# view-board.net
KiCad netlist of a schematic drawn in EAGLE
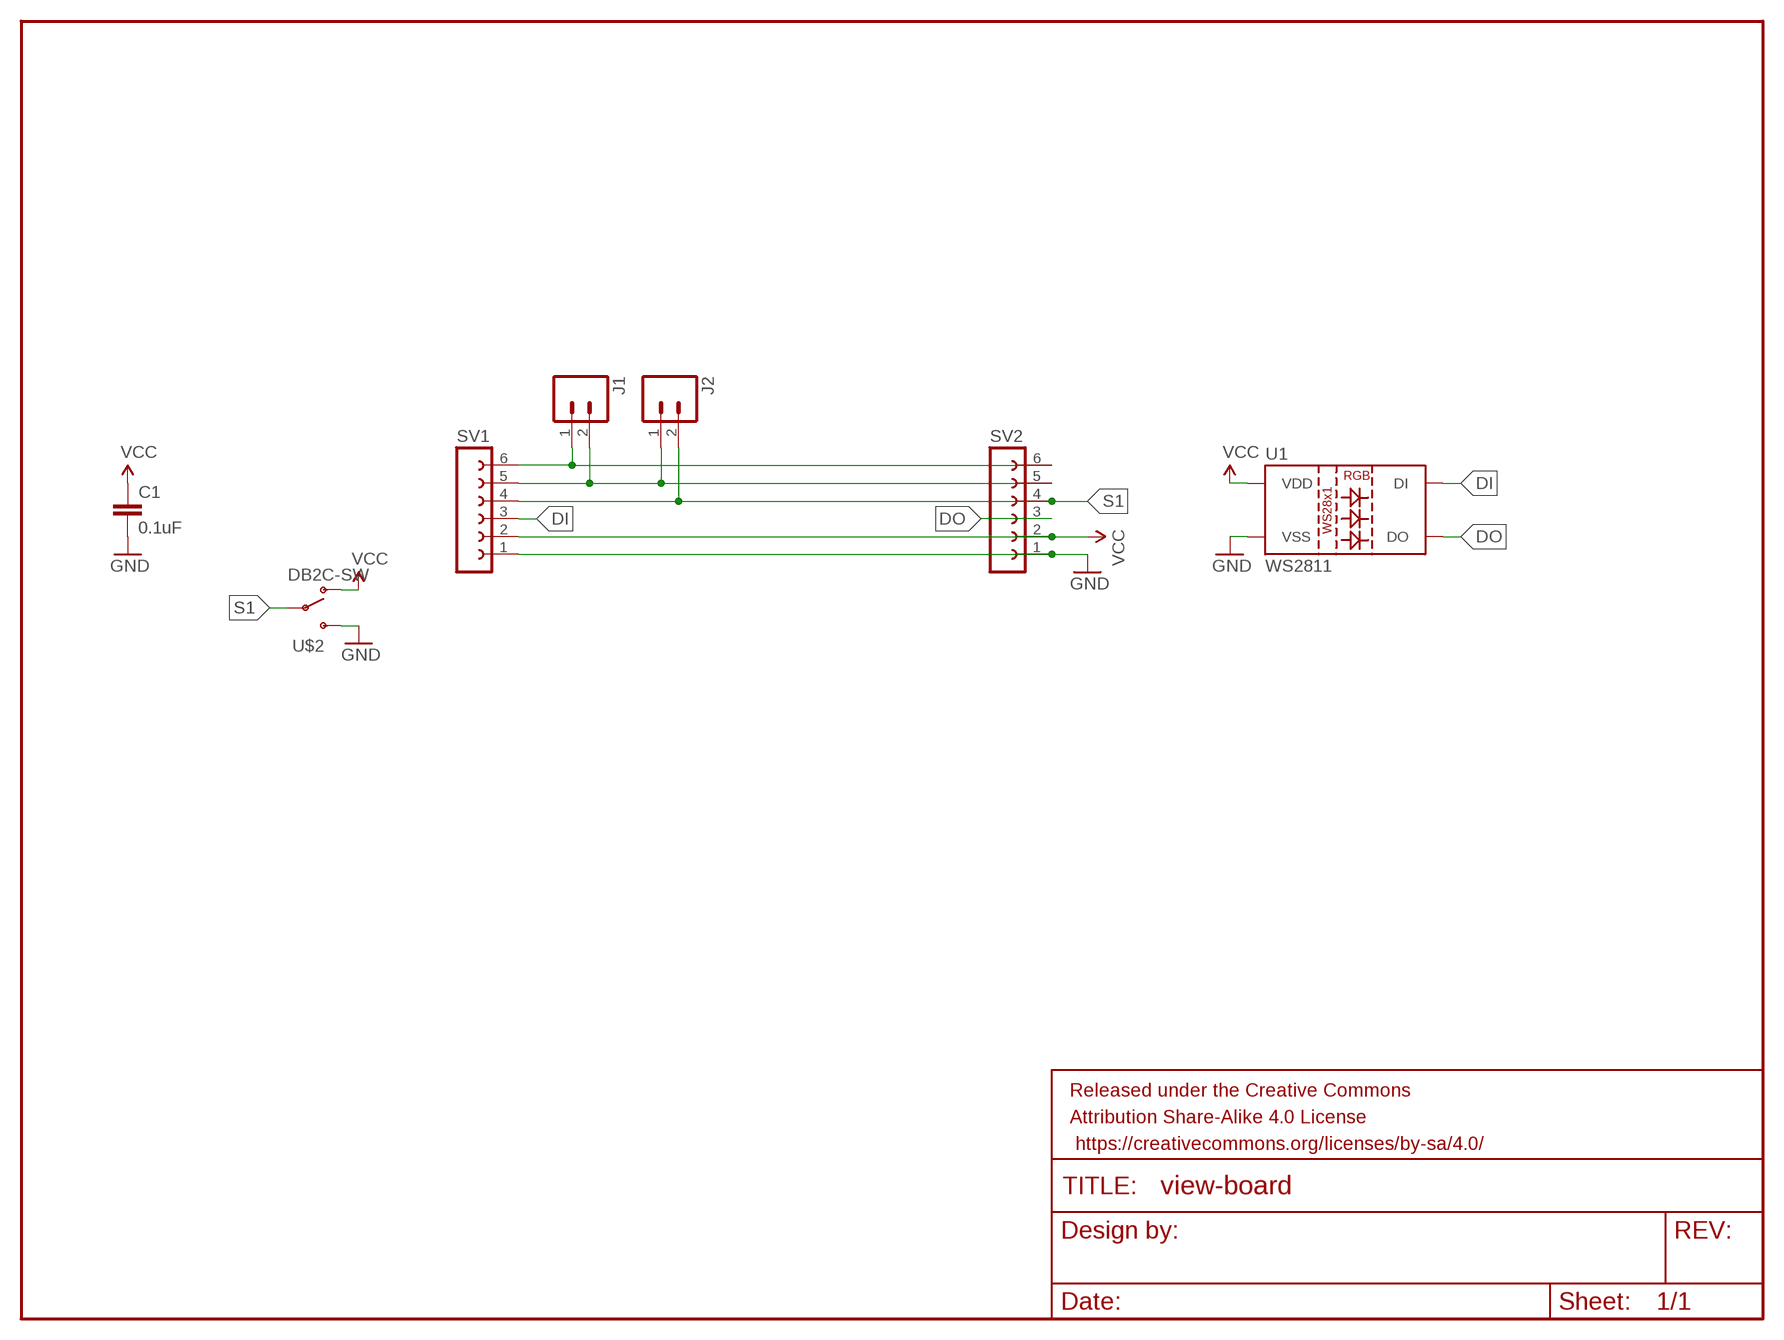
[diagram p0: schematic, sheet 1]

(export (version "E")
  (design (tool "Eeschema 10.0.6"))
  (components
    (comp (ref "C1")
      (value "0.1uF")
      (footprint "eagle-import:0805")
      (libsource (lib "eagle-import") (part "CAP0805"))
    )
    (comp (ref "FRAME1")
      (value "FRAME-LETTER")
      (footprint "eagle-import:CREATIVE_COMMONS")
      (libsource (lib "eagle-import") (part "FRAME-LETTER"))
    )
    (comp (ref "J1")
      (value "M02LOCK")
      (footprint "eagle-import:1X02_LOCK")
      (libsource (lib "eagle-import") (part "M02LOCK"))
    )
    (comp (ref "J2")
      (value "M02LOCK")
      (footprint "eagle-import:1X02_LOCK")
      (libsource (lib "eagle-import") (part "M02LOCK"))
    )
    (comp (ref "SV1")
      (value "FE06-1")
      (footprint "eagle-import:FE06")
      (libsource (lib "eagle-import") (part "FE06-1"))
    )
    (comp (ref "SV2")
      (value "FE06-1")
      (footprint "eagle-import:FE06")
      (libsource (lib "eagle-import") (part "FE06-1"))
    )
    (comp (ref "U$2")
      (value "DB2C-SW")
      (footprint "eagle-import:CHERRY-DB2C")
      (libsource (lib "eagle-import") (part "DB2C-SW"))
    )
    (comp (ref "U1")
      (value "WS2811")
      (footprint "eagle-import:LED-TRICOLOR-5050-IC")
      (libsource (lib "eagle-import") (part "LED-TRICOLOR-5050-ICWS2811"))
    )
  )
  (nets
    (net (code "1") (name "DI") (class "Default")
      (node (ref "SV1") (pin "3") (pinfunction "3_3") (pintype "passive"))
      (node (ref "U1") (pin "2") (pinfunction "DI_2") (pintype "bidirectional"))
    )
    (net (code "2") (name "DO") (class "Default")
      (node (ref "SV2") (pin "3") (pinfunction "3_3") (pintype "passive"))
      (node (ref "U1") (pin "1") (pinfunction "DO_1") (pintype "bidirectional"))
    )
    (net (code "3") (name "GND") (class "Default")
      (node (ref "C1") (pin "2") (pinfunction "2_2") (pintype "passive"))
      (node (ref "SV1") (pin "1") (pinfunction "1_1") (pintype "passive"))
      (node (ref "SV2") (pin "1") (pinfunction "1_1") (pintype "passive"))
      (node (ref "U$2") (pin "3") (pinfunction "S_3") (pintype "passive"))
      (node (ref "U1") (pin "6") (pinfunction "VSS_6") (pintype "bidirectional"))
    )
    (net (code "4") (name "Net-(J1-Pad1)") (class "Default")
      (node (ref "J1") (pin "1") (pinfunction "1_1") (pintype "passive"))
      (node (ref "SV1") (pin "6") (pinfunction "6_6") (pintype "passive"))
      (node (ref "SV2") (pin "6") (pinfunction "6_6") (pintype "passive"))
    )
    (net (code "5") (name "Net-(J1-Pad2)") (class "Default")
      (node (ref "J1") (pin "2") (pinfunction "2_2") (pintype "passive"))
      (node (ref "J2") (pin "1") (pinfunction "1_1") (pintype "passive"))
      (node (ref "SV1") (pin "5") (pinfunction "5_5") (pintype "passive"))
      (node (ref "SV2") (pin "5") (pinfunction "5_5") (pintype "passive"))
    )
    (net (code "6") (name "S1") (class "Default")
      (node (ref "J2") (pin "2") (pinfunction "2_2") (pintype "passive"))
      (node (ref "SV1") (pin "4") (pinfunction "4_4") (pintype "passive"))
      (node (ref "SV2") (pin "4") (pinfunction "4_4") (pintype "passive"))
      (node (ref "U$2") (pin "2") (pinfunction "P_2") (pintype "passive"))
    )
    (net (code "7") (name "VCC") (class "Default")
      (node (ref "C1") (pin "1") (pinfunction "1_1") (pintype "passive"))
      (node (ref "SV1") (pin "2") (pinfunction "2_2") (pintype "passive"))
      (node (ref "SV2") (pin "2") (pinfunction "2_2") (pintype "passive"))
      (node (ref "U$2") (pin "1") (pinfunction "O_1") (pintype "passive"))
      (node (ref "U1") (pin "3") (pinfunction "VDD_3") (pintype "bidirectional"))
      (node (ref "U1") (pin "5") (pinfunction "VDD_5") (pintype "bidirectional"))
    )
  )
)
